# ir_hid.net
KiCad netlist of a schematic drawn in EAGLE
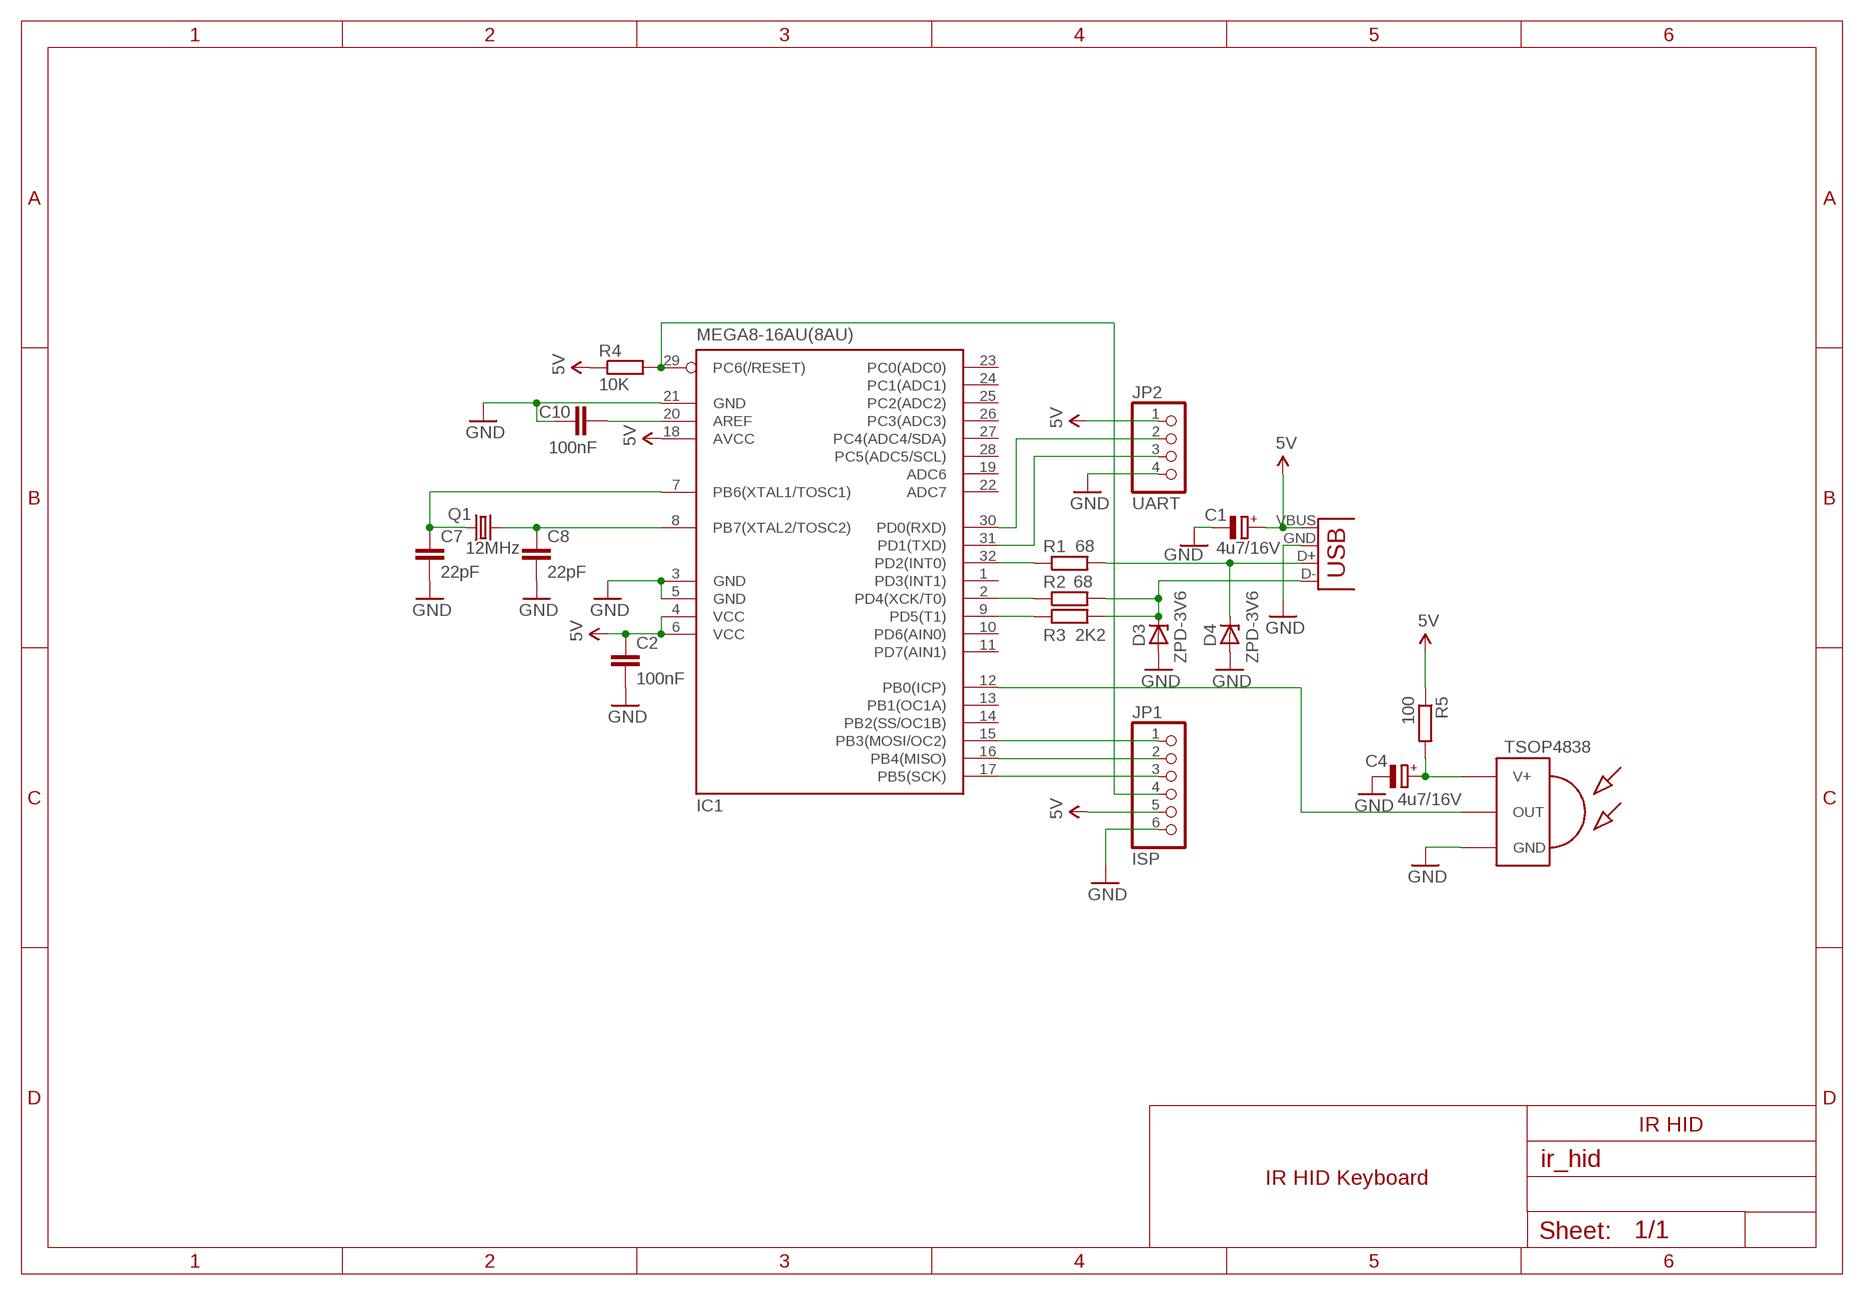
[diagram p0: schematic, sheet 1]

(export (version "E")
  (design (tool "Eeschema 10.0.6"))
  (components
    (comp (ref "C1")
      (value "4u7/16V")
      (footprint "eagle-import:E2,5-5")
      (libsource (lib "eagle-import") (part "CPOL-EUE2.5-5"))
    )
    (comp (ref "C2")
      (value "100nF")
      (footprint "eagle-import:C025-024X044")
      (libsource (lib "eagle-import") (part "C-EU025-024X044"))
    )
    (comp (ref "C4")
      (value "4u7/16V")
      (footprint "eagle-import:E2,5-5")
      (libsource (lib "eagle-import") (part "CPOL-EUE2.5-5"))
    )
    (comp (ref "C7")
      (value "22pF")
      (footprint "eagle-import:C025-024X044")
      (libsource (lib "eagle-import") (part "C-EU025-024X044"))
    )
    (comp (ref "C8")
      (value "22pF")
      (footprint "eagle-import:C025-024X044")
      (libsource (lib "eagle-import") (part "C-EU025-024X044"))
    )
    (comp (ref "C10")
      (value "100nF")
      (footprint "eagle-import:C025-024X044")
      (libsource (lib "eagle-import") (part "C-EU025-024X044"))
    )
    (comp (ref "D3")
      (value "ZPD-3V6")
      (footprint "eagle-import:DO35Z10")
      (libsource (lib "eagle-import") (part "ZPD"))
    )
    (comp (ref "D4")
      (value "ZPD-3V6")
      (footprint "eagle-import:DO35Z10")
      (libsource (lib "eagle-import") (part "ZPD"))
    )
    (comp (ref "IC1")
      (value "MEGA8-16AU(8AU)")
      (footprint "eagle-import:TQFP32-08")
      (fields (field (name "MPN") "ATMEGA8-16AU"))
      (libsource (lib "eagle-import") (part "MEGA8-AI"))
    )
    (comp (ref "JP1")
      (value "ISP")
      (footprint "eagle-import:1X06")
      (libsource (lib "eagle-import") (part "PINHD-1X6"))
    )
    (comp (ref "JP2")
      (value "UART")
      (footprint "eagle-import:1X04")
      (libsource (lib "eagle-import") (part "PINHD-1X4"))
    )
    (comp (ref "Q1")
      (value "12MHz")
      (footprint "eagle-import:HC49US")
      (libsource (lib "eagle-import") (part "CRYSTALHC49US"))
    )
    (comp (ref "R1")
      (value "68")
      (footprint "eagle-import:0207_10")
      (libsource (lib "eagle-import") (part "R-EU_0207/10"))
    )
    (comp (ref "R2")
      (value "68")
      (footprint "eagle-import:0207_10")
      (libsource (lib "eagle-import") (part "R-EU_0207/10"))
    )
    (comp (ref "R3")
      (value "2K2")
      (footprint "eagle-import:0207_10")
      (libsource (lib "eagle-import") (part "R-EU_0207/10"))
    )
    (comp (ref "R4")
      (value "10K")
      (footprint "eagle-import:0207_10")
      (libsource (lib "eagle-import") (part "R-EU_0207/10"))
    )
    (comp (ref "R5")
      (value "100")
      (footprint "eagle-import:0207_10")
      (libsource (lib "eagle-import") (part "R-EU_0207/10"))
    )
    (comp (ref "U$1")
      (value "TSOP4838")
      (footprint "eagle-import:TSOP18XX")
      (libsource (lib "eagle-import") (part "TSOP4838"))
    )
    (comp (ref "X1")
      (value "USBA-LP")
      (footprint "eagle-import:USB-A-H")
      (libsource (lib "eagle-import") (part "USB-A-H"))
    )
  )
  (nets
    (net (code "1") (name "5V") (class "Default")
      (node (ref "C1") (pin "+") (pinfunction "+_+") (pintype "passive"))
      (node (ref "C2") (pin "1") (pinfunction "1_1") (pintype "passive"))
      (node (ref "IC1") (pin "18") (pinfunction "AVCC_18") (pintype "power_in"))
      (node (ref "IC1") (pin "4") (pinfunction "VCC_4") (pintype "power_in"))
      (node (ref "IC1") (pin "6") (pinfunction "VCC_6") (pintype "power_in"))
      (node (ref "JP1") (pin "5") (pinfunction "5_5") (pintype "passive"))
      (node (ref "JP2") (pin "1") (pinfunction "1_1") (pintype "passive"))
      (node (ref "R4") (pin "1") (pinfunction "1_1") (pintype "passive"))
      (node (ref "R5") (pin "1") (pinfunction "1_1") (pintype "passive"))
      (node (ref "X1") (pin "VBUS") (pinfunction "GND_VBUS") (pintype "bidirectional"))
    )
    (net (code "2") (name "GND") (class "Default")
      (node (ref "C1") (pin "-") (pinfunction "-_-") (pintype "passive"))
      (node (ref "C10") (pin "1") (pinfunction "1_1") (pintype "passive"))
      (node (ref "C2") (pin "2") (pinfunction "2_2") (pintype "passive"))
      (node (ref "C4") (pin "-") (pinfunction "-_-") (pintype "passive"))
      (node (ref "C7") (pin "2") (pinfunction "2_2") (pintype "passive"))
      (node (ref "C8") (pin "2") (pinfunction "2_2") (pintype "passive"))
      (node (ref "D3") (pin "A") (pinfunction "A_A") (pintype "passive"))
      (node (ref "D4") (pin "A") (pinfunction "A_A") (pintype "passive"))
      (node (ref "IC1") (pin "21") (pinfunction "GND_21") (pintype "power_in"))
      (node (ref "IC1") (pin "3") (pinfunction "GND_3") (pintype "power_in"))
      (node (ref "IC1") (pin "5") (pinfunction "GND_5") (pintype "power_in"))
      (node (ref "JP1") (pin "6") (pinfunction "6_6") (pintype "passive"))
      (node (ref "JP2") (pin "4") (pinfunction "4_4") (pintype "passive"))
      (node (ref "U$1") (pin "GND") (pinfunction "GND_GND") (pintype "bidirectional"))
      (node (ref "X1") (pin "GND") (pinfunction "VBUS_GND") (pintype "bidirectional"))
    )
    (net (code "3") (name "Net-(IC1-AREF)") (class "Default")
      (node (ref "C10") (pin "2") (pinfunction "2_2") (pintype "passive"))
      (node (ref "IC1") (pin "20") (pinfunction "AREF_20") (pintype "passive"))
    )
    (net (code "4") (name "Net-(IC1-PB0(ICP))") (class "Default")
      (node (ref "IC1") (pin "12") (pinfunction "PB0(ICP)_12") (pintype "bidirectional"))
      (node (ref "U$1") (pin "OUT") (pinfunction "OUT_OUT") (pintype "bidirectional"))
    )
    (net (code "5") (name "Net-(IC1-PB3(MOSI{slash}OC2))") (class "Default")
      (node (ref "IC1") (pin "15") (pinfunction "PB3(MOSI/OC2)_15") (pintype "bidirectional"))
      (node (ref "JP1") (pin "1") (pinfunction "1_1") (pintype "passive"))
    )
    (net (code "6") (name "Net-(IC1-PB4(MISO))") (class "Default")
      (node (ref "IC1") (pin "16") (pinfunction "PB4(MISO)_16") (pintype "bidirectional"))
      (node (ref "JP1") (pin "2") (pinfunction "2_2") (pintype "passive"))
    )
    (net (code "7") (name "Net-(IC1-PB5(SCK))") (class "Default")
      (node (ref "IC1") (pin "17") (pinfunction "PB5(SCK)_17") (pintype "bidirectional"))
      (node (ref "JP1") (pin "3") (pinfunction "3_3") (pintype "passive"))
    )
    (net (code "8") (name "Net-(IC1-PB6(XTAL1{slash}TOSC1))") (class "Default")
      (node (ref "C7") (pin "1") (pinfunction "1_1") (pintype "passive"))
      (node (ref "IC1") (pin "7") (pinfunction "PB6(XTAL1/TOSC1)_7") (pintype "bidirectional"))
      (node (ref "Q1") (pin "1") (pinfunction "1_1") (pintype "passive"))
    )
    (net (code "9") (name "Net-(IC1-PB7(XTAL2{slash}TOSC2))") (class "Default")
      (node (ref "C8") (pin "1") (pinfunction "1_1") (pintype "passive"))
      (node (ref "IC1") (pin "8") (pinfunction "PB7(XTAL2/TOSC2)_8") (pintype "bidirectional"))
      (node (ref "Q1") (pin "2") (pinfunction "2_2") (pintype "passive"))
    )
    (net (code "10") (name "Net-(IC1-PC6({slash}RESET))") (class "Default")
      (node (ref "IC1") (pin "29") (pinfunction "PC6(/RESET)_29") (pintype "bidirectional"))
      (node (ref "JP1") (pin "4") (pinfunction "4_4") (pintype "passive"))
      (node (ref "R4") (pin "2") (pinfunction "2_2") (pintype "passive"))
    )
    (net (code "11") (name "Net-(IC1-PD0(RXD))") (class "Default")
      (node (ref "IC1") (pin "30") (pinfunction "PD0(RXD)_30") (pintype "bidirectional"))
      (node (ref "JP2") (pin "2") (pinfunction "2_2") (pintype "passive"))
    )
    (net (code "12") (name "Net-(IC1-PD1(TXD))") (class "Default")
      (node (ref "IC1") (pin "31") (pinfunction "PD1(TXD)_31") (pintype "bidirectional"))
      (node (ref "JP2") (pin "3") (pinfunction "3_3") (pintype "passive"))
    )
    (net (code "13") (name "Net-(IC1-PD2(INT0))") (class "Default")
      (node (ref "IC1") (pin "32") (pinfunction "PD2(INT0)_32") (pintype "bidirectional"))
      (node (ref "R1") (pin "1") (pinfunction "1_1") (pintype "passive"))
    )
    (net (code "14") (name "Net-(IC1-PD4(XCK{slash}T0))") (class "Default")
      (node (ref "IC1") (pin "2") (pinfunction "PD4(XCK/T0)_2") (pintype "bidirectional"))
      (node (ref "R2") (pin "1") (pinfunction "1_1") (pintype "passive"))
    )
    (net (code "15") (name "Net-(IC1-PD5(T1))") (class "Default")
      (node (ref "IC1") (pin "9") (pinfunction "PD5(T1)_9") (pintype "bidirectional"))
      (node (ref "R3") (pin "1") (pinfunction "1_1") (pintype "passive"))
    )
    (net (code "16") (name "Net-(U$1-V+)") (class "Default")
      (node (ref "C4") (pin "+") (pinfunction "+_+") (pintype "passive"))
      (node (ref "R5") (pin "2") (pinfunction "2_2") (pintype "passive"))
      (node (ref "U$1") (pin "VCC") (pinfunction "V+_VCC") (pintype "bidirectional"))
    )
    (net (code "17") (name "Net-(X1-D+)") (class "Default")
      (node (ref "D3") (pin "C") (pinfunction "C_C") (pintype "passive"))
      (node (ref "R2") (pin "2") (pinfunction "2_2") (pintype "passive"))
      (node (ref "R3") (pin "2") (pinfunction "2_2") (pintype "passive"))
      (node (ref "X1") (pin "D-") (pinfunction "D+_D-") (pintype "bidirectional"))
    )
    (net (code "18") (name "Net-(X1-D-)") (class "Default")
      (node (ref "D4") (pin "C") (pinfunction "C_C") (pintype "passive"))
      (node (ref "R1") (pin "2") (pinfunction "2_2") (pintype "passive"))
      (node (ref "X1") (pin "D+") (pinfunction "D-_D+") (pintype "bidirectional"))
    )
    (net (code "19") (name "unconnected-(IC1-ADC6-Pad19)") (class "Default")
      (node (ref "IC1") (pin "19") (pinfunction "ADC6_19") (pintype "bidirectional"))
    )
    (net (code "20") (name "unconnected-(IC1-ADC7-Pad22)") (class "Default")
      (node (ref "IC1") (pin "22") (pinfunction "ADC7_22") (pintype "bidirectional"))
    )
    (net (code "21") (name "unconnected-(IC1-PB1(OC1A)-Pad13)") (class "Default")
      (node (ref "IC1") (pin "13") (pinfunction "PB1(OC1A)_13") (pintype "bidirectional"))
    )
    (net (code "22") (name "unconnected-(IC1-PB2(SS{slash}OC1B)-Pad14)") (class "Default")
      (node (ref "IC1") (pin "14") (pinfunction "PB2(SS/OC1B)_14") (pintype "bidirectional"))
    )
    (net (code "23") (name "unconnected-(IC1-PC0(ADC0)-Pad23)") (class "Default")
      (node (ref "IC1") (pin "23") (pinfunction "PC0(ADC0)_23") (pintype "bidirectional"))
    )
    (net (code "24") (name "unconnected-(IC1-PC1(ADC1)-Pad24)") (class "Default")
      (node (ref "IC1") (pin "24") (pinfunction "PC1(ADC1)_24") (pintype "bidirectional"))
    )
    (net (code "25") (name "unconnected-(IC1-PC2(ADC2)-Pad25)") (class "Default")
      (node (ref "IC1") (pin "25") (pinfunction "PC2(ADC2)_25") (pintype "bidirectional"))
    )
    (net (code "26") (name "unconnected-(IC1-PC3(ADC3)-Pad26)") (class "Default")
      (node (ref "IC1") (pin "26") (pinfunction "PC3(ADC3)_26") (pintype "bidirectional"))
    )
    (net (code "27") (name "unconnected-(IC1-PC4(ADC4{slash}SDA)-Pad27)") (class "Default")
      (node (ref "IC1") (pin "27") (pinfunction "PC4(ADC4/SDA)_27") (pintype "bidirectional"))
    )
    (net (code "28") (name "unconnected-(IC1-PC5(ADC5{slash}SCL)-Pad28)") (class "Default")
      (node (ref "IC1") (pin "28") (pinfunction "PC5(ADC5/SCL)_28") (pintype "bidirectional"))
    )
    (net (code "29") (name "unconnected-(IC1-PD3(INT1)-Pad1)") (class "Default")
      (node (ref "IC1") (pin "1") (pinfunction "PD3(INT1)_1") (pintype "bidirectional"))
    )
    (net (code "30") (name "unconnected-(IC1-PD6(AIN0)-Pad10)") (class "Default")
      (node (ref "IC1") (pin "10") (pinfunction "PD6(AIN0)_10") (pintype "bidirectional"))
    )
    (net (code "31") (name "unconnected-(IC1-PD7(AIN1)-Pad11)") (class "Default")
      (node (ref "IC1") (pin "11") (pinfunction "PD7(AIN1)_11") (pintype "bidirectional"))
    )
  )
)
